# CPLD.net
KiCad netlist of a schematic drawn in Altium Designer
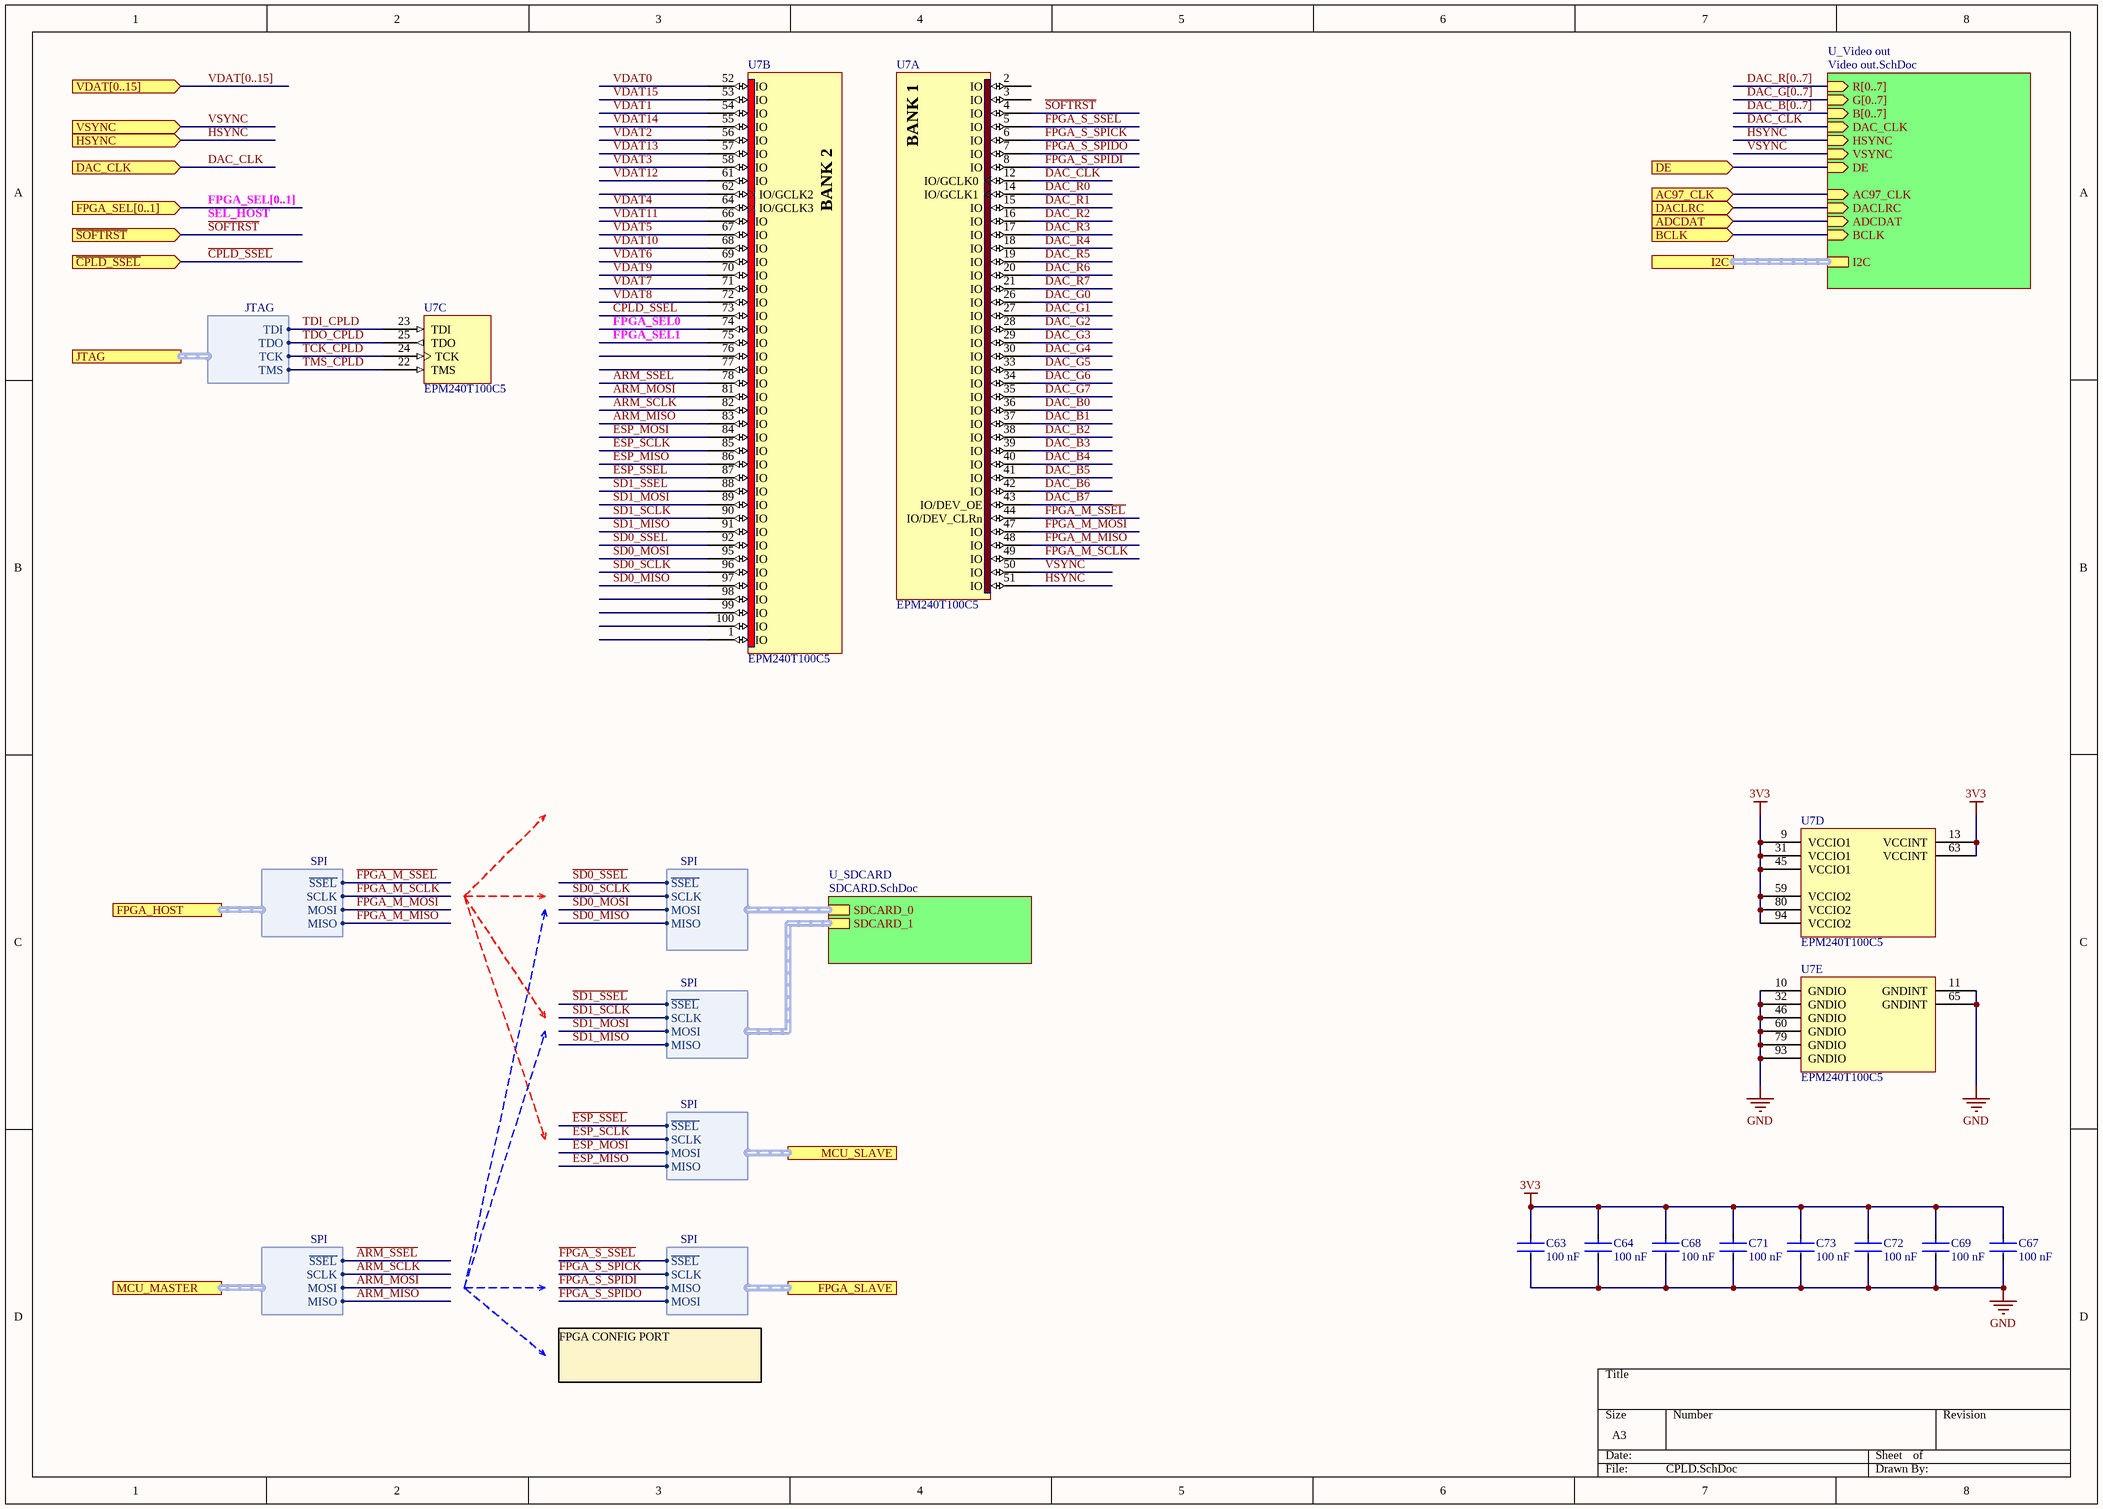
[diagram p0: CPLD.SchDoc]

(export (version "E")
  (design (tool "Eeschema 10.0.6"))
  (components
    (comp (ref "C63")
      (value "CC0805KRX7R9BB104")
      (footprint "FP-CC0805-0_85-IPC_A")
      (description "CAP CER 0.1UF 50V X7R 0805")
      (fields (field (name "MANUFACTURER") "Yageo") (field (name "CAPACITANCE") "100 nF"))
      (libsource (lib "SchLib") (part "CMP-2100-03606-3"))
    )
    (comp (ref "C64")
      (value "CC0805KRX7R9BB104")
      (footprint "FP-CC0805-0_85-IPC_A")
      (description "CAP CER 0.1UF 50V X7R 0805")
      (fields (field (name "MANUFACTURER") "Yageo") (field (name "CAPACITANCE") "100 nF"))
      (libsource (lib "SchLib") (part "CMP-2100-03606-3"))
    )
    (comp (ref "C67")
      (value "CC0805KRX7R9BB104")
      (footprint "FP-CC0805-0_85-IPC_A")
      (description "CAP CER 0.1UF 50V X7R 0805")
      (fields (field (name "MANUFACTURER") "Yageo") (field (name "CAPACITANCE") "100 nF"))
      (libsource (lib "SchLib") (part "CMP-2100-03606-3"))
    )
    (comp (ref "C68")
      (value "CC0805KRX7R9BB104")
      (footprint "FP-CC0805-0_85-IPC_A")
      (description "CAP CER 0.1UF 50V X7R 0805")
      (fields (field (name "MANUFACTURER") "Yageo") (field (name "CAPACITANCE") "100 nF"))
      (libsource (lib "SchLib") (part "CMP-2100-03606-3"))
    )
    (comp (ref "C69")
      (value "CC0805KRX7R9BB104")
      (footprint "FP-CC0805-0_85-IPC_A")
      (description "CAP CER 0.1UF 50V X7R 0805")
      (fields (field (name "MANUFACTURER") "Yageo") (field (name "CAPACITANCE") "100 nF"))
      (libsource (lib "SchLib") (part "CMP-2100-03606-3"))
    )
    (comp (ref "C71")
      (value "CC0805KRX7R9BB104")
      (footprint "FP-CC0805-0_85-IPC_A")
      (description "CAP CER 0.1UF 50V X7R 0805")
      (fields (field (name "MANUFACTURER") "Yageo") (field (name "CAPACITANCE") "100 nF"))
      (libsource (lib "SchLib") (part "CMP-2100-03606-3"))
    )
    (comp (ref "C72")
      (value "CC0805KRX7R9BB104")
      (footprint "FP-CC0805-0_85-IPC_A")
      (description "CAP CER 0.1UF 50V X7R 0805")
      (fields (field (name "MANUFACTURER") "Yageo") (field (name "CAPACITANCE") "100 nF"))
      (libsource (lib "SchLib") (part "CMP-2100-03606-3"))
    )
    (comp (ref "C73")
      (value "CC0805KRX7R9BB104")
      (footprint "FP-CC0805-0_85-IPC_A")
      (description "CAP CER 0.1UF 50V X7R 0805")
      (fields (field (name "MANUFACTURER") "Yageo") (field (name "CAPACITANCE") "100 nF"))
      (libsource (lib "SchLib") (part "CMP-2100-03606-3"))
    )
    (comp (ref "U7")
      (value "EPM240T100C5")
      (footprint "TQFP100_M")
      (fields (field (name "MANUFACTURER") "Intel Altera"))
      (libsource (lib "SchLib") (part "CMP-0144-00216-1"))
    )
  )
  (nets
    (net (code "6") (name "/ARM_MISO") (class "Default")
      (node (ref "U7") (pin "83") (pinfunction "IO_83") (pintype "bidirectional"))
    )
    (net (code "7") (name "/ARM_MOSI") (class "Default")
      (node (ref "U7") (pin "81") (pinfunction "IO_81") (pintype "bidirectional"))
    )
    (net (code "8") (name "/ARM_SCLK") (class "Default")
      (node (ref "U7") (pin "82") (pinfunction "IO_82") (pintype "bidirectional"))
    )
    (net (code "11") (name "/DAC_B0") (class "Default")
      (node (ref "U7") (pin "36") (pinfunction "IO_36") (pintype "bidirectional"))
    )
    (net (code "12") (name "/DAC_B1") (class "Default")
      (node (ref "U7") (pin "37") (pinfunction "IO_37") (pintype "bidirectional"))
    )
    (net (code "13") (name "/DAC_B2") (class "Default")
      (node (ref "U7") (pin "38") (pinfunction "IO_38") (pintype "bidirectional"))
    )
    (net (code "14") (name "/DAC_B3") (class "Default")
      (node (ref "U7") (pin "39") (pinfunction "IO_39") (pintype "bidirectional"))
    )
    (net (code "15") (name "/DAC_B4") (class "Default")
      (node (ref "U7") (pin "40") (pinfunction "IO_40") (pintype "bidirectional"))
    )
    (net (code "16") (name "/DAC_B5") (class "Default")
      (node (ref "U7") (pin "41") (pinfunction "IO_41") (pintype "bidirectional"))
    )
    (net (code "17") (name "/DAC_B6") (class "Default")
      (node (ref "U7") (pin "42") (pinfunction "IO_42") (pintype "bidirectional"))
    )
    (net (code "18") (name "/DAC_B7") (class "Default")
      (node (ref "U7") (pin "43") (pinfunction "IO/DEV_OE_43") (pintype "bidirectional"))
    )
    (net (code "20") (name "/DAC_CLK") (class "Default")
      (node (ref "U7") (pin "12") (pinfunction "IO/GCLK0_12") (pintype "bidirectional"))
    )
    (net (code "21") (name "/DAC_G0") (class "Default")
      (node (ref "U7") (pin "26") (pinfunction "IO_26") (pintype "bidirectional"))
    )
    (net (code "22") (name "/DAC_G1") (class "Default")
      (node (ref "U7") (pin "27") (pinfunction "IO_27") (pintype "bidirectional"))
    )
    (net (code "23") (name "/DAC_G2") (class "Default")
      (node (ref "U7") (pin "28") (pinfunction "IO_28") (pintype "bidirectional"))
    )
    (net (code "24") (name "/DAC_G3") (class "Default")
      (node (ref "U7") (pin "29") (pinfunction "IO_29") (pintype "bidirectional"))
    )
    (net (code "25") (name "/DAC_G4") (class "Default")
      (node (ref "U7") (pin "30") (pinfunction "IO_30") (pintype "bidirectional"))
    )
    (net (code "26") (name "/DAC_G5") (class "Default")
      (node (ref "U7") (pin "33") (pinfunction "IO_33") (pintype "bidirectional"))
    )
    (net (code "27") (name "/DAC_G6") (class "Default")
      (node (ref "U7") (pin "34") (pinfunction "IO_34") (pintype "bidirectional"))
    )
    (net (code "28") (name "/DAC_G7") (class "Default")
      (node (ref "U7") (pin "35") (pinfunction "IO_35") (pintype "bidirectional"))
    )
    (net (code "30") (name "/DAC_R0") (class "Default")
      (node (ref "U7") (pin "14") (pinfunction "IO/GCLK1_14") (pintype "bidirectional"))
    )
    (net (code "31") (name "/DAC_R1") (class "Default")
      (node (ref "U7") (pin "15") (pinfunction "IO_15") (pintype "bidirectional"))
    )
    (net (code "32") (name "/DAC_R2") (class "Default")
      (node (ref "U7") (pin "16") (pinfunction "IO_16") (pintype "bidirectional"))
    )
    (net (code "33") (name "/DAC_R3") (class "Default")
      (node (ref "U7") (pin "17") (pinfunction "IO_17") (pintype "bidirectional"))
    )
    (net (code "34") (name "/DAC_R4") (class "Default")
      (node (ref "U7") (pin "18") (pinfunction "IO_18") (pintype "bidirectional"))
    )
    (net (code "35") (name "/DAC_R5") (class "Default")
      (node (ref "U7") (pin "19") (pinfunction "IO_19") (pintype "bidirectional"))
    )
    (net (code "36") (name "/DAC_R6") (class "Default")
      (node (ref "U7") (pin "20") (pinfunction "IO_20") (pintype "bidirectional"))
    )
    (net (code "37") (name "/DAC_R7") (class "Default")
      (node (ref "U7") (pin "21") (pinfunction "IO_21") (pintype "bidirectional"))
    )
    (net (code "40") (name "/ESP_MISO") (class "Default")
      (node (ref "U7") (pin "86") (pinfunction "IO_86") (pintype "bidirectional"))
    )
    (net (code "41") (name "/ESP_MOSI") (class "Default")
      (node (ref "U7") (pin "84") (pinfunction "IO_84") (pintype "bidirectional"))
    )
    (net (code "42") (name "/ESP_SCLK") (class "Default")
      (node (ref "U7") (pin "85") (pinfunction "IO_85") (pintype "bidirectional"))
    )
    (net (code "43") (name "/FPGA_M_MISO") (class "Default")
      (node (ref "U7") (pin "48") (pinfunction "IO_48") (pintype "bidirectional"))
    )
    (net (code "44") (name "/FPGA_M_MOSI") (class "Default")
      (node (ref "U7") (pin "47") (pinfunction "IO_47") (pintype "bidirectional"))
    )
    (net (code "45") (name "/FPGA_M_SCLK") (class "Default")
      (node (ref "U7") (pin "49") (pinfunction "IO_49") (pintype "bidirectional"))
    )
    (net (code "46") (name "/FPGA_SEL0") (class "Default")
      (node (ref "U7") (pin "74") (pinfunction "IO_74") (pintype "bidirectional"))
    )
    (net (code "47") (name "/FPGA_SEL1") (class "Default")
      (node (ref "U7") (pin "75") (pinfunction "IO_75") (pintype "bidirectional"))
    )
    (net (code "49") (name "/FPGA_S_SPICK") (class "Default")
      (node (ref "U7") (pin "6") (pinfunction "IO_6") (pintype "bidirectional"))
    )
    (net (code "50") (name "/FPGA_S_SPIDI") (class "Default")
      (node (ref "U7") (pin "8") (pinfunction "IO_8") (pintype "bidirectional"))
    )
    (net (code "51") (name "/FPGA_S_SPIDO") (class "Default")
      (node (ref "U7") (pin "7") (pinfunction "IO_7") (pintype "bidirectional"))
    )
    (net (code "52") (name "/HSYNC") (class "Default")
      (node (ref "U7") (pin "51") (pinfunction "IO_51") (pintype "bidirectional"))
    )
    (net (code "54") (name "/SD0_MISO") (class "Default")
      (node (ref "U7") (pin "97") (pinfunction "IO_97") (pintype "bidirectional"))
    )
    (net (code "55") (name "/SD0_MOSI") (class "Default")
      (node (ref "U7") (pin "95") (pinfunction "IO_95") (pintype "bidirectional"))
    )
    (net (code "56") (name "/SD0_SCLK") (class "Default")
      (node (ref "U7") (pin "96") (pinfunction "IO_96") (pintype "bidirectional"))
    )
    (net (code "57") (name "/SD1_MISO") (class "Default")
      (node (ref "U7") (pin "91") (pinfunction "IO_91") (pintype "bidirectional"))
    )
    (net (code "58") (name "/SD1_MOSI") (class "Default")
      (node (ref "U7") (pin "89") (pinfunction "IO_89") (pintype "bidirectional"))
    )
    (net (code "59") (name "/SD1_SCLK") (class "Default")
      (node (ref "U7") (pin "90") (pinfunction "IO_90") (pintype "bidirectional"))
    )
    (net (code "61") (name "/TCK_CPLD") (class "Default")
      (node (ref "U7") (pin "24") (pinfunction "TCK_24") (pintype "input"))
    )
    (net (code "62") (name "/TDI_CPLD") (class "Default")
      (node (ref "U7") (pin "23") (pinfunction "TDI_23") (pintype "input"))
    )
    (net (code "63") (name "/TDO_CPLD") (class "Default")
      (node (ref "U7") (pin "25") (pinfunction "TDO_25") (pintype "output"))
    )
    (net (code "64") (name "/TMS_CPLD") (class "Default")
      (node (ref "U7") (pin "22") (pinfunction "TMS_22") (pintype "input"))
    )
    (net (code "65") (name "/VDAT0") (class "Default")
      (node (ref "U7") (pin "52") (pinfunction "IO_52") (pintype "bidirectional"))
    )
    (net (code "66") (name "/VDAT1") (class "Default")
      (node (ref "U7") (pin "54") (pinfunction "IO_54") (pintype "bidirectional"))
    )
    (net (code "67") (name "/VDAT2") (class "Default")
      (node (ref "U7") (pin "56") (pinfunction "IO_56") (pintype "bidirectional"))
    )
    (net (code "68") (name "/VDAT3") (class "Default")
      (node (ref "U7") (pin "58") (pinfunction "IO_58") (pintype "bidirectional"))
    )
    (net (code "69") (name "/VDAT4") (class "Default")
      (node (ref "U7") (pin "64") (pinfunction "IO/GCLK3_64") (pintype "bidirectional"))
    )
    (net (code "70") (name "/VDAT5") (class "Default")
      (node (ref "U7") (pin "67") (pinfunction "IO_67") (pintype "bidirectional"))
    )
    (net (code "71") (name "/VDAT6") (class "Default")
      (node (ref "U7") (pin "69") (pinfunction "IO_69") (pintype "bidirectional"))
    )
    (net (code "72") (name "/VDAT7") (class "Default")
      (node (ref "U7") (pin "71") (pinfunction "IO_71") (pintype "bidirectional"))
    )
    (net (code "73") (name "/VDAT8") (class "Default")
      (node (ref "U7") (pin "72") (pinfunction "IO_72") (pintype "bidirectional"))
    )
    (net (code "74") (name "/VDAT9") (class "Default")
      (node (ref "U7") (pin "70") (pinfunction "IO_70") (pintype "bidirectional"))
    )
    (net (code "75") (name "/VDAT10") (class "Default")
      (node (ref "U7") (pin "68") (pinfunction "IO_68") (pintype "bidirectional"))
    )
    (net (code "76") (name "/VDAT11") (class "Default")
      (node (ref "U7") (pin "66") (pinfunction "IO_66") (pintype "bidirectional"))
    )
    (net (code "77") (name "/VDAT12") (class "Default")
      (node (ref "U7") (pin "61") (pinfunction "IO_61") (pintype "bidirectional"))
    )
    (net (code "78") (name "/VDAT13") (class "Default")
      (node (ref "U7") (pin "57") (pinfunction "IO_57") (pintype "bidirectional"))
    )
    (net (code "79") (name "/VDAT14") (class "Default")
      (node (ref "U7") (pin "55") (pinfunction "IO_55") (pintype "bidirectional"))
    )
    (net (code "80") (name "/VDAT15") (class "Default")
      (node (ref "U7") (pin "53") (pinfunction "IO_53") (pintype "bidirectional"))
    )
    (net (code "82") (name "/VSYNC") (class "Default")
      (node (ref "U7") (pin "50") (pinfunction "IO_50") (pintype "bidirectional"))
    )
    (net (code "85") (name "/~{ARM_SSEL}") (class "Default")
      (node (ref "U7") (pin "78") (pinfunction "IO_78") (pintype "bidirectional"))
    )
    (net (code "86") (name "/~{CPLD_SSEL}") (class "Default")
      (node (ref "U7") (pin "73") (pinfunction "IO_73") (pintype "bidirectional"))
    )
    (net (code "87") (name "/~{ESP_SSEL}") (class "Default")
      (node (ref "U7") (pin "87") (pinfunction "IO_87") (pintype "bidirectional"))
    )
    (net (code "88") (name "/~{FPGA_M_SSEL}") (class "Default")
      (node (ref "U7") (pin "44") (pinfunction "IO/DEV_CLRn_44") (pintype "bidirectional"))
    )
    (net (code "89") (name "/~{FPGA_S_SSEL}") (class "Default")
      (node (ref "U7") (pin "5") (pinfunction "IO_5") (pintype "bidirectional"))
    )
    (net (code "90") (name "/~{SD0_SSEL}") (class "Default")
      (node (ref "U7") (pin "92") (pinfunction "IO_92") (pintype "bidirectional"))
    )
    (net (code "91") (name "/~{SD1_SSEL}") (class "Default")
      (node (ref "U7") (pin "88") (pinfunction "IO_88") (pintype "bidirectional"))
    )
    (net (code "92") (name "/~{SOFTRST}") (class "Default")
      (node (ref "U7") (pin "4") (pinfunction "IO_4") (pintype "bidirectional"))
    )
    (net (code "93") (name "3V3") (class "Default")
      (node (ref "C63") (pin "1") (pinfunction "1_1") (pintype "passive"))
      (node (ref "C64") (pin "1") (pinfunction "1_1") (pintype "passive"))
      (node (ref "C67") (pin "1") (pinfunction "1_1") (pintype "passive"))
      (node (ref "C68") (pin "1") (pinfunction "1_1") (pintype "passive"))
      (node (ref "C69") (pin "1") (pinfunction "1_1") (pintype "passive"))
      (node (ref "C71") (pin "1") (pinfunction "1_1") (pintype "passive"))
      (node (ref "C72") (pin "1") (pinfunction "1_1") (pintype "passive"))
      (node (ref "C73") (pin "1") (pinfunction "1_1") (pintype "passive"))
      (node (ref "U7") (pin "13") (pinfunction "VCCINT_13") (pintype "power_in"))
      (node (ref "U7") (pin "31") (pinfunction "VCCIO1_31") (pintype "power_in"))
      (node (ref "U7") (pin "45") (pinfunction "VCCIO1_45") (pintype "power_in"))
      (node (ref "U7") (pin "59") (pinfunction "VCCIO2_59") (pintype "power_in"))
      (node (ref "U7") (pin "63") (pinfunction "VCCINT_63") (pintype "power_in"))
      (node (ref "U7") (pin "80") (pinfunction "VCCIO2_80") (pintype "power_in"))
      (node (ref "U7") (pin "9") (pinfunction "VCCIO1_9") (pintype "power_in"))
      (node (ref "U7") (pin "94") (pinfunction "VCCIO2_94") (pintype "power_in"))
    )
    (net (code "94") (name "GND") (class "Default")
      (node (ref "C63") (pin "2") (pinfunction "2_2") (pintype "passive"))
      (node (ref "C64") (pin "2") (pinfunction "2_2") (pintype "passive"))
      (node (ref "C67") (pin "2") (pinfunction "2_2") (pintype "passive"))
      (node (ref "C68") (pin "2") (pinfunction "2_2") (pintype "passive"))
      (node (ref "C69") (pin "2") (pinfunction "2_2") (pintype "passive"))
      (node (ref "C71") (pin "2") (pinfunction "2_2") (pintype "passive"))
      (node (ref "C72") (pin "2") (pinfunction "2_2") (pintype "passive"))
      (node (ref "C73") (pin "2") (pinfunction "2_2") (pintype "passive"))
      (node (ref "U7") (pin "10") (pinfunction "GNDIO_10") (pintype "power_in"))
      (node (ref "U7") (pin "11") (pinfunction "GNDINT_11") (pintype "power_in"))
      (node (ref "U7") (pin "32") (pinfunction "GNDIO_32") (pintype "power_in"))
      (node (ref "U7") (pin "46") (pinfunction "GNDIO_46") (pintype "power_in"))
      (node (ref "U7") (pin "60") (pinfunction "GNDIO_60") (pintype "power_in"))
      (node (ref "U7") (pin "65") (pinfunction "GNDINT_65") (pintype "power_in"))
      (node (ref "U7") (pin "79") (pinfunction "GNDIO_79") (pintype "power_in"))
      (node (ref "U7") (pin "93") (pinfunction "GNDIO_93") (pintype "power_in"))
    )
    (net (code "95") (name "unconnected-(U7A-IO-Pad2)") (class "Default")
      (node (ref "U7") (pin "2") (pinfunction "IO_2") (pintype "bidirectional"))
    )
    (net (code "96") (name "unconnected-(U7A-IO-Pad3)") (class "Default")
      (node (ref "U7") (pin "3") (pinfunction "IO_3") (pintype "bidirectional"))
    )
    (net (code "97") (name "unconnected-(U7B-IO-Pad1)") (class "Default")
      (node (ref "U7") (pin "1") (pinfunction "IO_1") (pintype "bidirectional"))
    )
    (net (code "98") (name "unconnected-(U7B-IO-Pad76)") (class "Default")
      (node (ref "U7") (pin "76") (pinfunction "IO_76") (pintype "bidirectional"))
    )
    (net (code "99") (name "unconnected-(U7B-IO-Pad77)") (class "Default")
      (node (ref "U7") (pin "77") (pinfunction "IO_77") (pintype "bidirectional"))
    )
    (net (code "100") (name "unconnected-(U7B-IO-Pad98)") (class "Default")
      (node (ref "U7") (pin "98") (pinfunction "IO_98") (pintype "bidirectional"))
    )
    (net (code "101") (name "unconnected-(U7B-IO-Pad99)") (class "Default")
      (node (ref "U7") (pin "99") (pinfunction "IO_99") (pintype "bidirectional"))
    )
    (net (code "102") (name "unconnected-(U7B-IO-Pad100)") (class "Default")
      (node (ref "U7") (pin "100") (pinfunction "IO_100") (pintype "bidirectional"))
    )
    (net (code "103") (name "unconnected-(U7B-IO{slash}GCLK2-Pad62)") (class "Default")
      (node (ref "U7") (pin "62") (pinfunction "IO/GCLK2_62") (pintype "bidirectional"))
    )
  )
)
